# backplane_v1_1-nochips.net
KiCad netlist of a schematic drawn in EAGLE
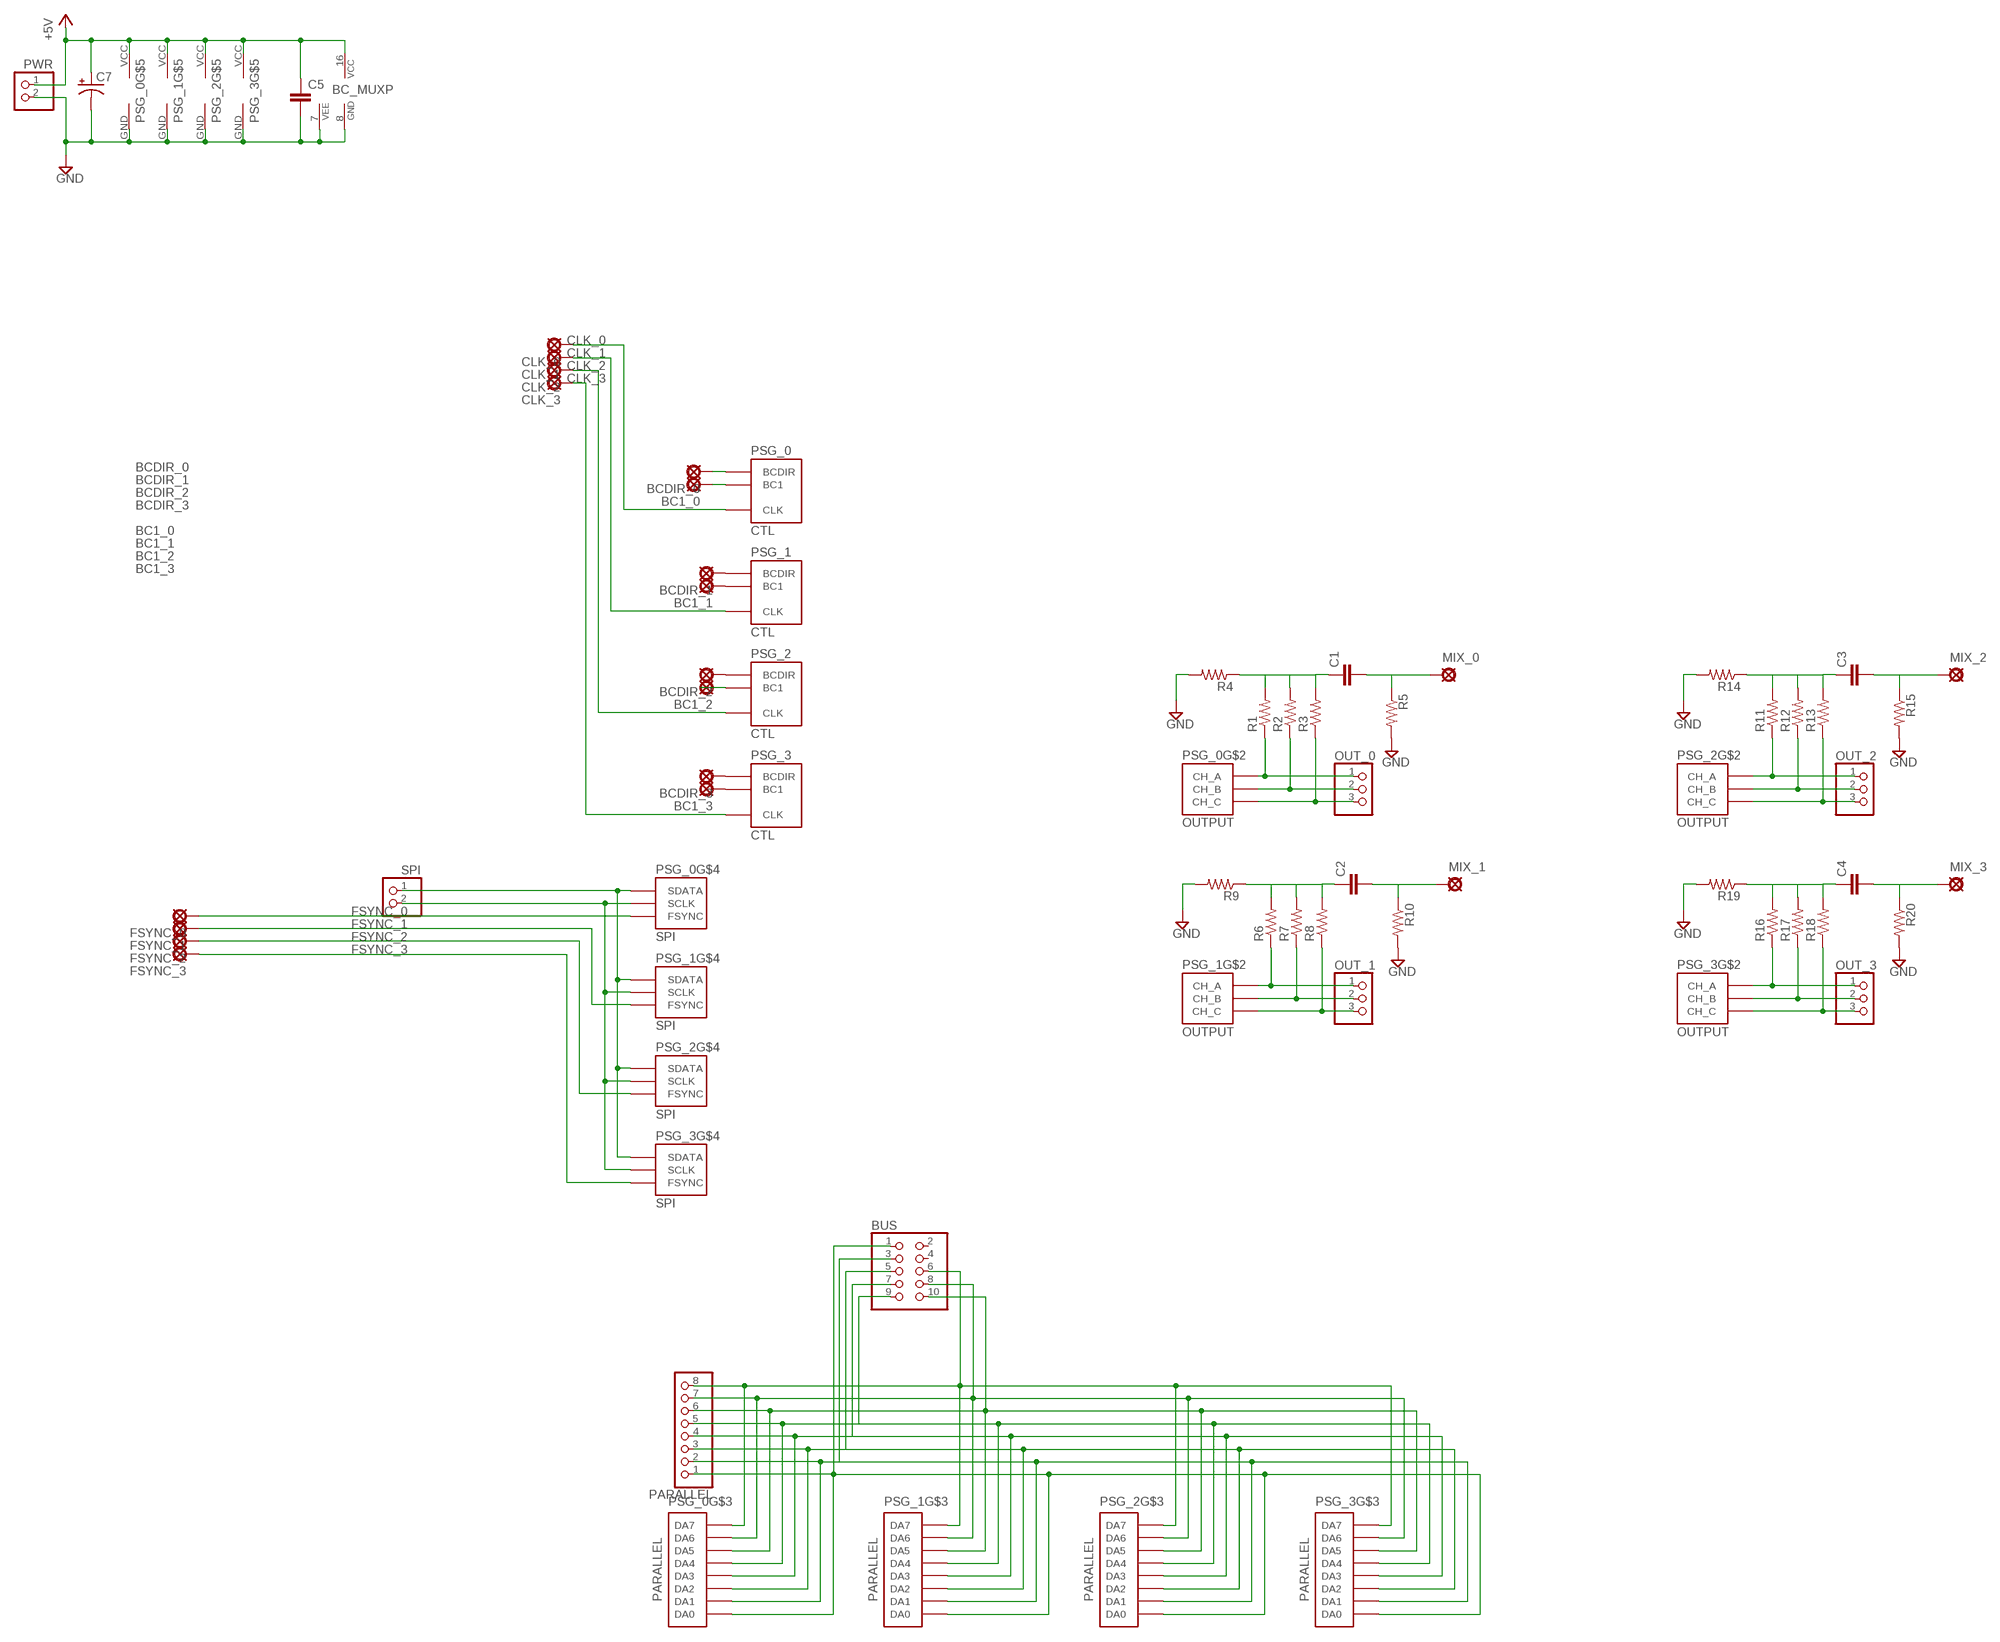
[diagram p0: schematic, sheet 1]

(export (version "E")
  (design (tool "Eeschema 10.0.6"))
  (components
    (comp (ref "BC1_0")
      (value "PAD")
      (footprint "eagle-import:SQUARE")
      (libsource (lib "eagle-import") (part "PAD"))
    )
    (comp (ref "BC1_1")
      (value "PAD")
      (footprint "eagle-import:SQUARE")
      (libsource (lib "eagle-import") (part "PAD"))
    )
    (comp (ref "BC1_2")
      (value "PAD")
      (footprint "eagle-import:SQUARE")
      (libsource (lib "eagle-import") (part "PAD"))
    )
    (comp (ref "BC1_3")
      (value "PAD")
      (footprint "eagle-import:SQUARE")
      (libsource (lib "eagle-import") (part "PAD"))
    )
    (comp (ref "BCDIR_0")
      (value "PAD")
      (footprint "eagle-import:SQUARE")
      (libsource (lib "eagle-import") (part "PAD"))
    )
    (comp (ref "BCDIR_1")
      (value "PAD")
      (footprint "eagle-import:SQUARE")
      (libsource (lib "eagle-import") (part "PAD"))
    )
    (comp (ref "BCDIR_2")
      (value "PAD")
      (footprint "eagle-import:SQUARE")
      (libsource (lib "eagle-import") (part "PAD"))
    )
    (comp (ref "BCDIR_3")
      (value "PAD")
      (footprint "eagle-import:SQUARE")
      (libsource (lib "eagle-import") (part "PAD"))
    )
    (comp (ref "BC_MUX")
      (value "4052N")
      (footprint "eagle-import:DIL16")
      (libsource (lib "eagle-import") (part "4052N"))
    )
    (comp (ref "BUS")
      (value "PINHD-2X5IDC")
      (footprint "eagle-import:10PIN_IDC")
      (libsource (lib "eagle-import") (part "PINHD-2X5IDC"))
    )
    (comp (ref "C1")
      (value "070X0302")
      (footprint "eagle-import:070X030")
      (libsource (lib "eagle-import") (part "070X0302"))
    )
    (comp (ref "C2")
      (value "070X0302")
      (footprint "eagle-import:070X030")
      (libsource (lib "eagle-import") (part "070X0302"))
    )
    (comp (ref "C3")
      (value "070X0302")
      (footprint "eagle-import:070X030")
      (libsource (lib "eagle-import") (part "070X0302"))
    )
    (comp (ref "C4")
      (value "070X0302")
      (footprint "eagle-import:070X030")
      (libsource (lib "eagle-import") (part "070X0302"))
    )
    (comp (ref "C5")
      (value "050X030_0251")
      (footprint "eagle-import:050X030_025")
      (libsource (lib "eagle-import") (part "050X030_0251"))
    )
    (comp (ref "C7")
      (value "0631")
      (footprint "eagle-import:063_025")
      (libsource (lib "eagle-import") (part "0631"))
    )
    (comp (ref "CLK_0")
      (value "PAD")
      (footprint "eagle-import:SQUARE")
      (libsource (lib "eagle-import") (part "PAD"))
    )
    (comp (ref "CLK_1")
      (value "PAD")
      (footprint "eagle-import:SQUARE")
      (libsource (lib "eagle-import") (part "PAD"))
    )
    (comp (ref "CLK_2")
      (value "PAD")
      (footprint "eagle-import:SQUARE")
      (libsource (lib "eagle-import") (part "PAD"))
    )
    (comp (ref "CLK_3")
      (value "PAD")
      (footprint "eagle-import:SQUARE")
      (libsource (lib "eagle-import") (part "PAD"))
    )
    (comp (ref "FSYNC_0")
      (value "PAD")
      (footprint "eagle-import:SQUARE")
      (libsource (lib "eagle-import") (part "PAD"))
    )
    (comp (ref "FSYNC_1")
      (value "PAD")
      (footprint "eagle-import:SQUARE")
      (libsource (lib "eagle-import") (part "PAD"))
    )
    (comp (ref "FSYNC_2")
      (value "PAD")
      (footprint "eagle-import:SQUARE")
      (libsource (lib "eagle-import") (part "PAD"))
    )
    (comp (ref "FSYNC_3")
      (value "PAD")
      (footprint "eagle-import:SQUARE")
      (libsource (lib "eagle-import") (part "PAD"))
    )
    (comp (ref "MIX_0")
      (value "PAD")
      (footprint "eagle-import:SQUARE")
      (libsource (lib "eagle-import") (part "PAD"))
    )
    (comp (ref "MIX_1")
      (value "PAD")
      (footprint "eagle-import:SQUARE")
      (libsource (lib "eagle-import") (part "PAD"))
    )
    (comp (ref "MIX_2")
      (value "PAD")
      (footprint "eagle-import:SQUARE")
      (libsource (lib "eagle-import") (part "PAD"))
    )
    (comp (ref "MIX_3")
      (value "PAD")
      (footprint "eagle-import:SQUARE")
      (libsource (lib "eagle-import") (part "PAD"))
    )
    (comp (ref "OUT_0")
      (value "PINHD-1X3")
      (footprint "eagle-import:1X03")
      (libsource (lib "eagle-import") (part "PINHD-1X3"))
    )
    (comp (ref "OUT_1")
      (value "PINHD-1X3")
      (footprint "eagle-import:1X03")
      (libsource (lib "eagle-import") (part "PINHD-1X3"))
    )
    (comp (ref "OUT_2")
      (value "PINHD-1X3")
      (footprint "eagle-import:1X03")
      (libsource (lib "eagle-import") (part "PINHD-1X3"))
    )
    (comp (ref "OUT_3")
      (value "PINHD-1X3")
      (footprint "eagle-import:1X03")
      (libsource (lib "eagle-import") (part "PINHD-1X3"))
    )
    (comp (ref "PARALLEL")
      (value "PINHD-1X8")
      (footprint "eagle-import:1X08")
      (libsource (lib "eagle-import") (part "PINHD-1X8"))
    )
    (comp (ref "PSG_0")
      (value "PSG_DAUGHTER")
      (footprint "eagle-import:PSG_DAUGHTER")
      (libsource (lib "eagle-import") (part "PSG_DAUGHTER"))
    )
    (comp (ref "PSG_1")
      (value "PSG_DAUGHTER")
      (footprint "eagle-import:PSG_DAUGHTER")
      (libsource (lib "eagle-import") (part "PSG_DAUGHTER"))
    )
    (comp (ref "PSG_2")
      (value "PSG_DAUGHTER")
      (footprint "eagle-import:PSG_DAUGHTER")
      (libsource (lib "eagle-import") (part "PSG_DAUGHTER"))
    )
    (comp (ref "PSG_3")
      (value "PSG_DAUGHTER")
      (footprint "eagle-import:PSG_DAUGHTER")
      (libsource (lib "eagle-import") (part "PSG_DAUGHTER"))
    )
    (comp (ref "PWR")
      (value "PINHD-1X2")
      (footprint "eagle-import:1X02")
      (libsource (lib "eagle-import") (part "PINHD-1X2"))
    )
    (comp (ref "R1")
      (value "6MM.3")
      (footprint "eagle-import:R0207_3")
      (libsource (lib "eagle-import") (part "6MM.3"))
    )
    (comp (ref "R2")
      (value "6MM.3")
      (footprint "eagle-import:R0207_3")
      (libsource (lib "eagle-import") (part "6MM.3"))
    )
    (comp (ref "R3")
      (value "6MM.3")
      (footprint "eagle-import:R0207_3")
      (libsource (lib "eagle-import") (part "6MM.3"))
    )
    (comp (ref "R4")
      (value "6MM.3")
      (footprint "eagle-import:R0207_3")
      (libsource (lib "eagle-import") (part "6MM.3"))
    )
    (comp (ref "R5")
      (value "6MM.3")
      (footprint "eagle-import:R0207_3")
      (libsource (lib "eagle-import") (part "6MM.3"))
    )
    (comp (ref "R6")
      (value "6MM.3")
      (footprint "eagle-import:R0207_3")
      (libsource (lib "eagle-import") (part "6MM.3"))
    )
    (comp (ref "R7")
      (value "6MM.3")
      (footprint "eagle-import:R0207_3")
      (libsource (lib "eagle-import") (part "6MM.3"))
    )
    (comp (ref "R8")
      (value "6MM.3")
      (footprint "eagle-import:R0207_3")
      (libsource (lib "eagle-import") (part "6MM.3"))
    )
    (comp (ref "R9")
      (value "6MM.3")
      (footprint "eagle-import:R0207_3")
      (libsource (lib "eagle-import") (part "6MM.3"))
    )
    (comp (ref "R10")
      (value "6MM.3")
      (footprint "eagle-import:R0207_3")
      (libsource (lib "eagle-import") (part "6MM.3"))
    )
    (comp (ref "R11")
      (value "6MM.3")
      (footprint "eagle-import:R0207_3")
      (libsource (lib "eagle-import") (part "6MM.3"))
    )
    (comp (ref "R12")
      (value "6MM.3")
      (footprint "eagle-import:R0207_3")
      (libsource (lib "eagle-import") (part "6MM.3"))
    )
    (comp (ref "R13")
      (value "6MM.3")
      (footprint "eagle-import:R0207_3")
      (libsource (lib "eagle-import") (part "6MM.3"))
    )
    (comp (ref "R14")
      (value "6MM.3")
      (footprint "eagle-import:R0207_3")
      (libsource (lib "eagle-import") (part "6MM.3"))
    )
    (comp (ref "R15")
      (value "6MM.3")
      (footprint "eagle-import:R0207_3")
      (libsource (lib "eagle-import") (part "6MM.3"))
    )
    (comp (ref "R16")
      (value "6MM.3")
      (footprint "eagle-import:R0207_3")
      (libsource (lib "eagle-import") (part "6MM.3"))
    )
    (comp (ref "R17")
      (value "6MM.3")
      (footprint "eagle-import:R0207_3")
      (libsource (lib "eagle-import") (part "6MM.3"))
    )
    (comp (ref "R18")
      (value "6MM.3")
      (footprint "eagle-import:R0207_3")
      (libsource (lib "eagle-import") (part "6MM.3"))
    )
    (comp (ref "R19")
      (value "6MM.3")
      (footprint "eagle-import:R0207_3")
      (libsource (lib "eagle-import") (part "6MM.3"))
    )
    (comp (ref "R20")
      (value "6MM.3")
      (footprint "eagle-import:R0207_3")
      (libsource (lib "eagle-import") (part "6MM.3"))
    )
    (comp (ref "SPI")
      (value "PINHD-1X2")
      (footprint "eagle-import:1X02")
      (libsource (lib "eagle-import") (part "PINHD-1X2"))
    )
  )
  (nets
    (net (code "1") (name "+5V") (class "Default")
      (node (ref "BC_MUX") (pin "16") (pinfunction "VCC_16") (pintype "power_in"))
      (node (ref "C5") (pin "1") (pinfunction "1_1") (pintype "passive"))
      (node (ref "C7") (pin "+") (pinfunction "+_+") (pintype "passive"))
      (node (ref "PSG_0") (pin "VCC") (pinfunction "VCC_VCC") (pintype "power_in"))
      (node (ref "PSG_1") (pin "VCC") (pinfunction "VCC_VCC") (pintype "power_in"))
      (node (ref "PSG_2") (pin "VCC") (pinfunction "VCC_VCC") (pintype "power_in"))
      (node (ref "PSG_3") (pin "VCC") (pinfunction "VCC_VCC") (pintype "power_in"))
      (node (ref "PWR") (pin "1") (pinfunction "1_1") (pintype "passive"))
    )
    (net (code "2") (name "/BC1_0") (class "Default")
      (node (ref "BC1_0") (pin "1") (pinfunction "PAD_1") (pintype "passive"))
      (node (ref "PSG_0") (pin "BC1") (pinfunction "BC1_BC1") (pintype "input"))
    )
    (net (code "4") (name "/BC1_1") (class "Default")
      (node (ref "BC1_1") (pin "1") (pinfunction "PAD_1") (pintype "passive"))
      (node (ref "PSG_1") (pin "BC1") (pinfunction "BC1_BC1") (pintype "input"))
    )
    (net (code "6") (name "/BC1_2") (class "Default")
      (node (ref "BC1_2") (pin "1") (pinfunction "PAD_1") (pintype "passive"))
      (node (ref "PSG_2") (pin "BC1") (pinfunction "BC1_BC1") (pintype "input"))
    )
    (net (code "10") (name "/BC1_3") (class "Default")
      (node (ref "BC1_3") (pin "1") (pinfunction "PAD_1") (pintype "passive"))
      (node (ref "PSG_3") (pin "BC1") (pinfunction "BC1_BC1") (pintype "input"))
    )
    (net (code "11") (name "/BCDIR_0") (class "Default")
      (node (ref "BCDIR_0") (pin "1") (pinfunction "PAD_1") (pintype "passive"))
      (node (ref "PSG_0") (pin "BCDIR") (pinfunction "BCDIR_BCDIR") (pintype "input"))
    )
    (net (code "12") (name "/BCDIR_1") (class "Default")
      (node (ref "BCDIR_1") (pin "1") (pinfunction "PAD_1") (pintype "passive"))
      (node (ref "PSG_1") (pin "BCDIR") (pinfunction "BCDIR_BCDIR") (pintype "input"))
    )
    (net (code "13") (name "/BCDIR_2") (class "Default")
      (node (ref "BCDIR_2") (pin "1") (pinfunction "PAD_1") (pintype "passive"))
      (node (ref "PSG_2") (pin "BCDIR") (pinfunction "BCDIR_BCDIR") (pintype "input"))
    )
    (net (code "14") (name "/BCDIR_3") (class "Default")
      (node (ref "BCDIR_3") (pin "1") (pinfunction "PAD_1") (pintype "passive"))
      (node (ref "PSG_3") (pin "BCDIR") (pinfunction "BCDIR_BCDIR") (pintype "input"))
    )
    (net (code "15") (name "/CLK_0") (class "Default")
      (node (ref "CLK_0") (pin "1") (pinfunction "PAD_1") (pintype "passive"))
      (node (ref "PSG_0") (pin "CLK") (pinfunction "CLK_CLK") (pintype "input"))
    )
    (net (code "16") (name "/CLK_1") (class "Default")
      (node (ref "CLK_1") (pin "1") (pinfunction "PAD_1") (pintype "passive"))
      (node (ref "PSG_1") (pin "CLK") (pinfunction "CLK_CLK") (pintype "input"))
    )
    (net (code "17") (name "/CLK_2") (class "Default")
      (node (ref "CLK_2") (pin "1") (pinfunction "PAD_1") (pintype "passive"))
      (node (ref "PSG_2") (pin "CLK") (pinfunction "CLK_CLK") (pintype "input"))
    )
    (net (code "18") (name "/CLK_3") (class "Default")
      (node (ref "CLK_3") (pin "1") (pinfunction "PAD_1") (pintype "passive"))
      (node (ref "PSG_3") (pin "CLK") (pinfunction "CLK_CLK") (pintype "input"))
    )
    (net (code "19") (name "/FSYNC_0") (class "Default")
      (node (ref "FSYNC_0") (pin "1") (pinfunction "PAD_1") (pintype "passive"))
      (node (ref "PSG_0") (pin "FSYNC") (pinfunction "FSYNC_FSYNC") (pintype "input"))
    )
    (net (code "20") (name "/FSYNC_1") (class "Default")
      (node (ref "FSYNC_1") (pin "1") (pinfunction "PAD_1") (pintype "passive"))
      (node (ref "PSG_1") (pin "FSYNC") (pinfunction "FSYNC_FSYNC") (pintype "input"))
    )
    (net (code "21") (name "/FSYNC_2") (class "Default")
      (node (ref "FSYNC_2") (pin "1") (pinfunction "PAD_1") (pintype "passive"))
      (node (ref "PSG_2") (pin "FSYNC") (pinfunction "FSYNC_FSYNC") (pintype "input"))
    )
    (net (code "22") (name "/FSYNC_3") (class "Default")
      (node (ref "FSYNC_3") (pin "1") (pinfunction "PAD_1") (pintype "passive"))
      (node (ref "PSG_3") (pin "FSYNC") (pinfunction "FSYNC_FSYNC") (pintype "input"))
    )
    (net (code "23") (name "GND") (class "Default")
      (node (ref "BC_MUX") (pin "7") (pinfunction "VEE_7") (pintype "power_in"))
      (node (ref "BC_MUX") (pin "8") (pinfunction "GND_8") (pintype "power_in"))
      (node (ref "C5") (pin "2") (pinfunction "2_2") (pintype "passive"))
      (node (ref "C7") (pin "-") (pinfunction "-_-") (pintype "passive"))
      (node (ref "PSG_0") (pin "GND") (pinfunction "GND_GND") (pintype "power_in"))
      (node (ref "PSG_1") (pin "GND") (pinfunction "GND_GND") (pintype "power_in"))
      (node (ref "PSG_2") (pin "GND") (pinfunction "GND_GND") (pintype "power_in"))
      (node (ref "PSG_3") (pin "GND") (pinfunction "GND_GND") (pintype "power_in"))
      (node (ref "PWR") (pin "2") (pinfunction "2_2") (pintype "passive"))
      (node (ref "R10") (pin "2") (pinfunction "2_2") (pintype "passive"))
      (node (ref "R14") (pin "2") (pinfunction "2_2") (pintype "passive"))
      (node (ref "R15") (pin "2") (pinfunction "2_2") (pintype "passive"))
      (node (ref "R19") (pin "2") (pinfunction "2_2") (pintype "passive"))
      (node (ref "R20") (pin "2") (pinfunction "2_2") (pintype "passive"))
      (node (ref "R4") (pin "2") (pinfunction "2_2") (pintype "passive"))
      (node (ref "R5") (pin "2") (pinfunction "2_2") (pintype "passive"))
      (node (ref "R9") (pin "2") (pinfunction "2_2") (pintype "passive"))
    )
    (net (code "24") (name "Net-(BUS-Pad1)") (class "Default")
      (node (ref "BUS") (pin "1") (pinfunction "1_1") (pintype "passive"))
      (node (ref "PARALLEL") (pin "1") (pinfunction "1_1") (pintype "passive"))
      (node (ref "PSG_0") (pin "DA0") (pinfunction "DA0_DA0") (pintype "bidirectional"))
      (node (ref "PSG_1") (pin "DA0") (pinfunction "DA0_DA0") (pintype "bidirectional"))
      (node (ref "PSG_2") (pin "DA0") (pinfunction "DA0_DA0") (pintype "bidirectional"))
      (node (ref "PSG_3") (pin "DA0") (pinfunction "DA0_DA0") (pintype "bidirectional"))
    )
    (net (code "25") (name "Net-(BUS-Pad3)") (class "Default")
      (node (ref "BUS") (pin "3") (pinfunction "3_3") (pintype "passive"))
      (node (ref "PARALLEL") (pin "2") (pinfunction "2_2") (pintype "passive"))
      (node (ref "PSG_0") (pin "DA1") (pinfunction "DA1_DA1") (pintype "bidirectional"))
      (node (ref "PSG_1") (pin "DA1") (pinfunction "DA1_DA1") (pintype "bidirectional"))
      (node (ref "PSG_2") (pin "DA1") (pinfunction "DA1_DA1") (pintype "bidirectional"))
      (node (ref "PSG_3") (pin "DA1") (pinfunction "DA1_DA1") (pintype "bidirectional"))
    )
    (net (code "26") (name "Net-(BUS-Pad5)") (class "Default")
      (node (ref "BUS") (pin "5") (pinfunction "5_5") (pintype "passive"))
      (node (ref "PARALLEL") (pin "3") (pinfunction "3_3") (pintype "passive"))
      (node (ref "PSG_0") (pin "DA2") (pinfunction "DA2_DA2") (pintype "bidirectional"))
      (node (ref "PSG_1") (pin "DA2") (pinfunction "DA2_DA2") (pintype "bidirectional"))
      (node (ref "PSG_2") (pin "DA2") (pinfunction "DA2_DA2") (pintype "bidirectional"))
      (node (ref "PSG_3") (pin "DA2") (pinfunction "DA2_DA2") (pintype "bidirectional"))
    )
    (net (code "27") (name "Net-(BUS-Pad6)") (class "Default")
      (node (ref "BUS") (pin "6") (pinfunction "6_6") (pintype "passive"))
      (node (ref "PARALLEL") (pin "8") (pinfunction "8_8") (pintype "passive"))
      (node (ref "PSG_0") (pin "DA7") (pinfunction "DA7_DA7") (pintype "bidirectional"))
      (node (ref "PSG_1") (pin "DA7") (pinfunction "DA7_DA7") (pintype "bidirectional"))
      (node (ref "PSG_2") (pin "DA7") (pinfunction "DA7_DA7") (pintype "bidirectional"))
      (node (ref "PSG_3") (pin "DA7") (pinfunction "DA7_DA7") (pintype "bidirectional"))
    )
    (net (code "28") (name "Net-(BUS-Pad7)") (class "Default")
      (node (ref "BUS") (pin "7") (pinfunction "7_7") (pintype "passive"))
      (node (ref "PARALLEL") (pin "4") (pinfunction "4_4") (pintype "passive"))
      (node (ref "PSG_0") (pin "DA3") (pinfunction "DA3_DA3") (pintype "bidirectional"))
      (node (ref "PSG_1") (pin "DA3") (pinfunction "DA3_DA3") (pintype "bidirectional"))
      (node (ref "PSG_2") (pin "DA3") (pinfunction "DA3_DA3") (pintype "bidirectional"))
      (node (ref "PSG_3") (pin "DA3") (pinfunction "DA3_DA3") (pintype "bidirectional"))
    )
    (net (code "29") (name "Net-(BUS-Pad8)") (class "Default")
      (node (ref "BUS") (pin "8") (pinfunction "8_8") (pintype "passive"))
      (node (ref "PARALLEL") (pin "7") (pinfunction "7_7") (pintype "passive"))
      (node (ref "PSG_0") (pin "DA6") (pinfunction "DA6_DA6") (pintype "bidirectional"))
      (node (ref "PSG_1") (pin "DA6") (pinfunction "DA6_DA6") (pintype "bidirectional"))
      (node (ref "PSG_2") (pin "DA6") (pinfunction "DA6_DA6") (pintype "bidirectional"))
      (node (ref "PSG_3") (pin "DA6") (pinfunction "DA6_DA6") (pintype "bidirectional"))
    )
    (net (code "30") (name "Net-(BUS-Pad9)") (class "Default")
      (node (ref "BUS") (pin "9") (pinfunction "9_9") (pintype "passive"))
      (node (ref "PARALLEL") (pin "5") (pinfunction "5_5") (pintype "passive"))
      (node (ref "PSG_0") (pin "DA4") (pinfunction "DA4_DA4") (pintype "bidirectional"))
      (node (ref "PSG_1") (pin "DA4") (pinfunction "DA4_DA4") (pintype "bidirectional"))
      (node (ref "PSG_2") (pin "DA4") (pinfunction "DA4_DA4") (pintype "bidirectional"))
      (node (ref "PSG_3") (pin "DA4") (pinfunction "DA4_DA4") (pintype "bidirectional"))
    )
    (net (code "31") (name "Net-(BUS-Pad10)") (class "Default")
      (node (ref "BUS") (pin "10") (pinfunction "10_10") (pintype "passive"))
      (node (ref "PARALLEL") (pin "6") (pinfunction "6_6") (pintype "passive"))
      (node (ref "PSG_0") (pin "DA5") (pinfunction "DA5_DA5") (pintype "bidirectional"))
      (node (ref "PSG_1") (pin "DA5") (pinfunction "DA5_DA5") (pintype "bidirectional"))
      (node (ref "PSG_2") (pin "DA5") (pinfunction "DA5_DA5") (pintype "bidirectional"))
      (node (ref "PSG_3") (pin "DA5") (pinfunction "DA5_DA5") (pintype "bidirectional"))
    )
    (net (code "32") (name "Net-(C1-Pad1)") (class "Default")
      (node (ref "C1") (pin "1") (pinfunction "1_1") (pintype "passive"))
      (node (ref "R1") (pin "2") (pinfunction "2_2") (pintype "passive"))
      (node (ref "R2") (pin "2") (pinfunction "2_2") (pintype "passive"))
      (node (ref "R3") (pin "2") (pinfunction "2_2") (pintype "passive"))
      (node (ref "R4") (pin "1") (pinfunction "1_1") (pintype "passive"))
    )
    (net (code "33") (name "Net-(C2-Pad1)") (class "Default")
      (node (ref "C2") (pin "1") (pinfunction "1_1") (pintype "passive"))
      (node (ref "R6") (pin "2") (pinfunction "2_2") (pintype "passive"))
      (node (ref "R7") (pin "2") (pinfunction "2_2") (pintype "passive"))
      (node (ref "R8") (pin "2") (pinfunction "2_2") (pintype "passive"))
      (node (ref "R9") (pin "1") (pinfunction "1_1") (pintype "passive"))
    )
    (net (code "34") (name "Net-(C3-Pad1)") (class "Default")
      (node (ref "C3") (pin "1") (pinfunction "1_1") (pintype "passive"))
      (node (ref "R11") (pin "2") (pinfunction "2_2") (pintype "passive"))
      (node (ref "R12") (pin "2") (pinfunction "2_2") (pintype "passive"))
      (node (ref "R13") (pin "2") (pinfunction "2_2") (pintype "passive"))
      (node (ref "R14") (pin "1") (pinfunction "1_1") (pintype "passive"))
    )
    (net (code "35") (name "Net-(C4-Pad1)") (class "Default")
      (node (ref "C4") (pin "1") (pinfunction "1_1") (pintype "passive"))
      (node (ref "R16") (pin "2") (pinfunction "2_2") (pintype "passive"))
      (node (ref "R17") (pin "2") (pinfunction "2_2") (pintype "passive"))
      (node (ref "R18") (pin "2") (pinfunction "2_2") (pintype "passive"))
      (node (ref "R19") (pin "1") (pinfunction "1_1") (pintype "passive"))
    )
    (net (code "36") (name "Net-(MIX_0-PAD)") (class "Default")
      (node (ref "C1") (pin "2") (pinfunction "2_2") (pintype "passive"))
      (node (ref "MIX_0") (pin "1") (pinfunction "PAD_1") (pintype "passive"))
      (node (ref "R5") (pin "1") (pinfunction "1_1") (pintype "passive"))
    )
    (net (code "37") (name "Net-(MIX_1-PAD)") (class "Default")
      (node (ref "C2") (pin "2") (pinfunction "2_2") (pintype "passive"))
      (node (ref "MIX_1") (pin "1") (pinfunction "PAD_1") (pintype "passive"))
      (node (ref "R10") (pin "1") (pinfunction "1_1") (pintype "passive"))
    )
    (net (code "38") (name "Net-(MIX_2-PAD)") (class "Default")
      (node (ref "C3") (pin "2") (pinfunction "2_2") (pintype "passive"))
      (node (ref "MIX_2") (pin "1") (pinfunction "PAD_1") (pintype "passive"))
      (node (ref "R15") (pin "1") (pinfunction "1_1") (pintype "passive"))
    )
    (net (code "39") (name "Net-(MIX_3-PAD)") (class "Default")
      (node (ref "C4") (pin "2") (pinfunction "2_2") (pintype "passive"))
      (node (ref "MIX_3") (pin "1") (pinfunction "PAD_1") (pintype "passive"))
      (node (ref "R20") (pin "1") (pinfunction "1_1") (pintype "passive"))
    )
    (net (code "40") (name "Net-(PSG_0-PadSCLK)") (class "Default")
      (node (ref "PSG_0") (pin "SCLK") (pinfunction "SCLK_SCLK") (pintype "input"))
      (node (ref "PSG_1") (pin "SCLK") (pinfunction "SCLK_SCLK") (pintype "input"))
      (node (ref "PSG_2") (pin "SCLK") (pinfunction "SCLK_SCLK") (pintype "input"))
      (node (ref "PSG_3") (pin "SCLK") (pinfunction "SCLK_SCLK") (pintype "input"))
      (node (ref "SPI") (pin "2") (pinfunction "2_2") (pintype "passive"))
    )
    (net (code "41") (name "Net-(PSG_0-PadSDATA)") (class "Default")
      (node (ref "PSG_0") (pin "SDATA") (pinfunction "SDATA_SDATA") (pintype "bidirectional"))
      (node (ref "PSG_1") (pin "SDATA") (pinfunction "SDATA_SDATA") (pintype "bidirectional"))
      (node (ref "PSG_2") (pin "SDATA") (pinfunction "SDATA_SDATA") (pintype "bidirectional"))
      (node (ref "PSG_3") (pin "SDATA") (pinfunction "SDATA_SDATA") (pintype "bidirectional"))
      (node (ref "SPI") (pin "1") (pinfunction "1_1") (pintype "passive"))
    )
    (net (code "42") (name "Net-(PSG_0B-CH_A)") (class "Default")
      (node (ref "OUT_0") (pin "1") (pinfunction "1_1") (pintype "passive"))
      (node (ref "PSG_0") (pin "OUT_A") (pinfunction "CH_A_OUT_A") (pintype "input"))
      (node (ref "R1") (pin "1") (pinfunction "1_1") (pintype "passive"))
    )
    (net (code "43") (name "Net-(PSG_0B-CH_B)") (class "Default")
      (node (ref "OUT_0") (pin "2") (pinfunction "2_2") (pintype "passive"))
      (node (ref "PSG_0") (pin "OUT_B") (pinfunction "CH_B_OUT_B") (pintype "input"))
      (node (ref "R2") (pin "1") (pinfunction "1_1") (pintype "passive"))
    )
    (net (code "44") (name "Net-(PSG_0B-CH_C)") (class "Default")
      (node (ref "OUT_0") (pin "3") (pinfunction "3_3") (pintype "passive"))
      (node (ref "PSG_0") (pin "OUT_C") (pinfunction "CH_C_OUT_C") (pintype "input"))
      (node (ref "R3") (pin "1") (pinfunction "1_1") (pintype "passive"))
    )
    (net (code "45") (name "Net-(PSG_1B-CH_A)") (class "Default")
      (node (ref "OUT_1") (pin "1") (pinfunction "1_1") (pintype "passive"))
      (node (ref "PSG_1") (pin "OUT_A") (pinfunction "CH_A_OUT_A") (pintype "input"))
      (node (ref "R6") (pin "1") (pinfunction "1_1") (pintype "passive"))
    )
    (net (code "46") (name "Net-(PSG_1B-CH_B)") (class "Default")
      (node (ref "OUT_1") (pin "2") (pinfunction "2_2") (pintype "passive"))
      (node (ref "PSG_1") (pin "OUT_B") (pinfunction "CH_B_OUT_B") (pintype "input"))
      (node (ref "R7") (pin "1") (pinfunction "1_1") (pintype "passive"))
    )
    (net (code "47") (name "Net-(PSG_1B-CH_C)") (class "Default")
      (node (ref "OUT_1") (pin "3") (pinfunction "3_3") (pintype "passive"))
      (node (ref "PSG_1") (pin "OUT_C") (pinfunction "CH_C_OUT_C") (pintype "input"))
      (node (ref "R8") (pin "1") (pinfunction "1_1") (pintype "passive"))
    )
    (net (code "48") (name "Net-(PSG_2B-CH_A)") (class "Default")
      (node (ref "OUT_2") (pin "1") (pinfunction "1_1") (pintype "passive"))
      (node (ref "PSG_2") (pin "OUT_A") (pinfunction "CH_A_OUT_A") (pintype "input"))
      (node (ref "R11") (pin "1") (pinfunction "1_1") (pintype "passive"))
    )
    (net (code "49") (name "Net-(PSG_2B-CH_B)") (class "Default")
      (node (ref "OUT_2") (pin "2") (pinfunction "2_2") (pintype "passive"))
      (node (ref "PSG_2") (pin "OUT_B") (pinfunction "CH_B_OUT_B") (pintype "input"))
      (node (ref "R12") (pin "1") (pinfunction "1_1") (pintype "passive"))
    )
    (net (code "50") (name "Net-(PSG_2B-CH_C)") (class "Default")
      (node (ref "OUT_2") (pin "3") (pinfunction "3_3") (pintype "passive"))
      (node (ref "PSG_2") (pin "OUT_C") (pinfunction "CH_C_OUT_C") (pintype "input"))
      (node (ref "R13") (pin "1") (pinfunction "1_1") (pintype "passive"))
    )
    (net (code "51") (name "Net-(PSG_3B-CH_A)") (class "Default")
      (node (ref "OUT_3") (pin "1") (pinfunction "1_1") (pintype "passive"))
      (node (ref "PSG_3") (pin "OUT_A") (pinfunction "CH_A_OUT_A") (pintype "input"))
      (node (ref "R16") (pin "1") (pinfunction "1_1") (pintype "passive"))
    )
    (net (code "52") (name "Net-(PSG_3B-CH_B)") (class "Default")
      (node (ref "OUT_3") (pin "2") (pinfunction "2_2") (pintype "passive"))
      (node (ref "PSG_3") (pin "OUT_B") (pinfunction "CH_B_OUT_B") (pintype "input"))
      (node (ref "R17") (pin "1") (pinfunction "1_1") (pintype "passive"))
    )
    (net (code "53") (name "Net-(PSG_3B-CH_C)") (class "Default")
      (node (ref "OUT_3") (pin "3") (pinfunction "3_3") (pintype "passive"))
      (node (ref "PSG_3") (pin "OUT_C") (pinfunction "CH_C_OUT_C") (pintype "input"))
      (node (ref "R18") (pin "1") (pinfunction "1_1") (pintype "passive"))
    )
    (net (code "54") (name "unconnected-(BUS-Pad2)") (class "Default")
      (node (ref "BUS") (pin "2") (pinfunction "2_2") (pintype "passive"))
    )
    (net (code "55") (name "unconnected-(BUS-Pad4)") (class "Default")
      (node (ref "BUS") (pin "4") (pinfunction "4_4") (pintype "passive"))
    )
  )
)
